# BluetoothMate.net
KiCad netlist of a schematic drawn in EAGLE
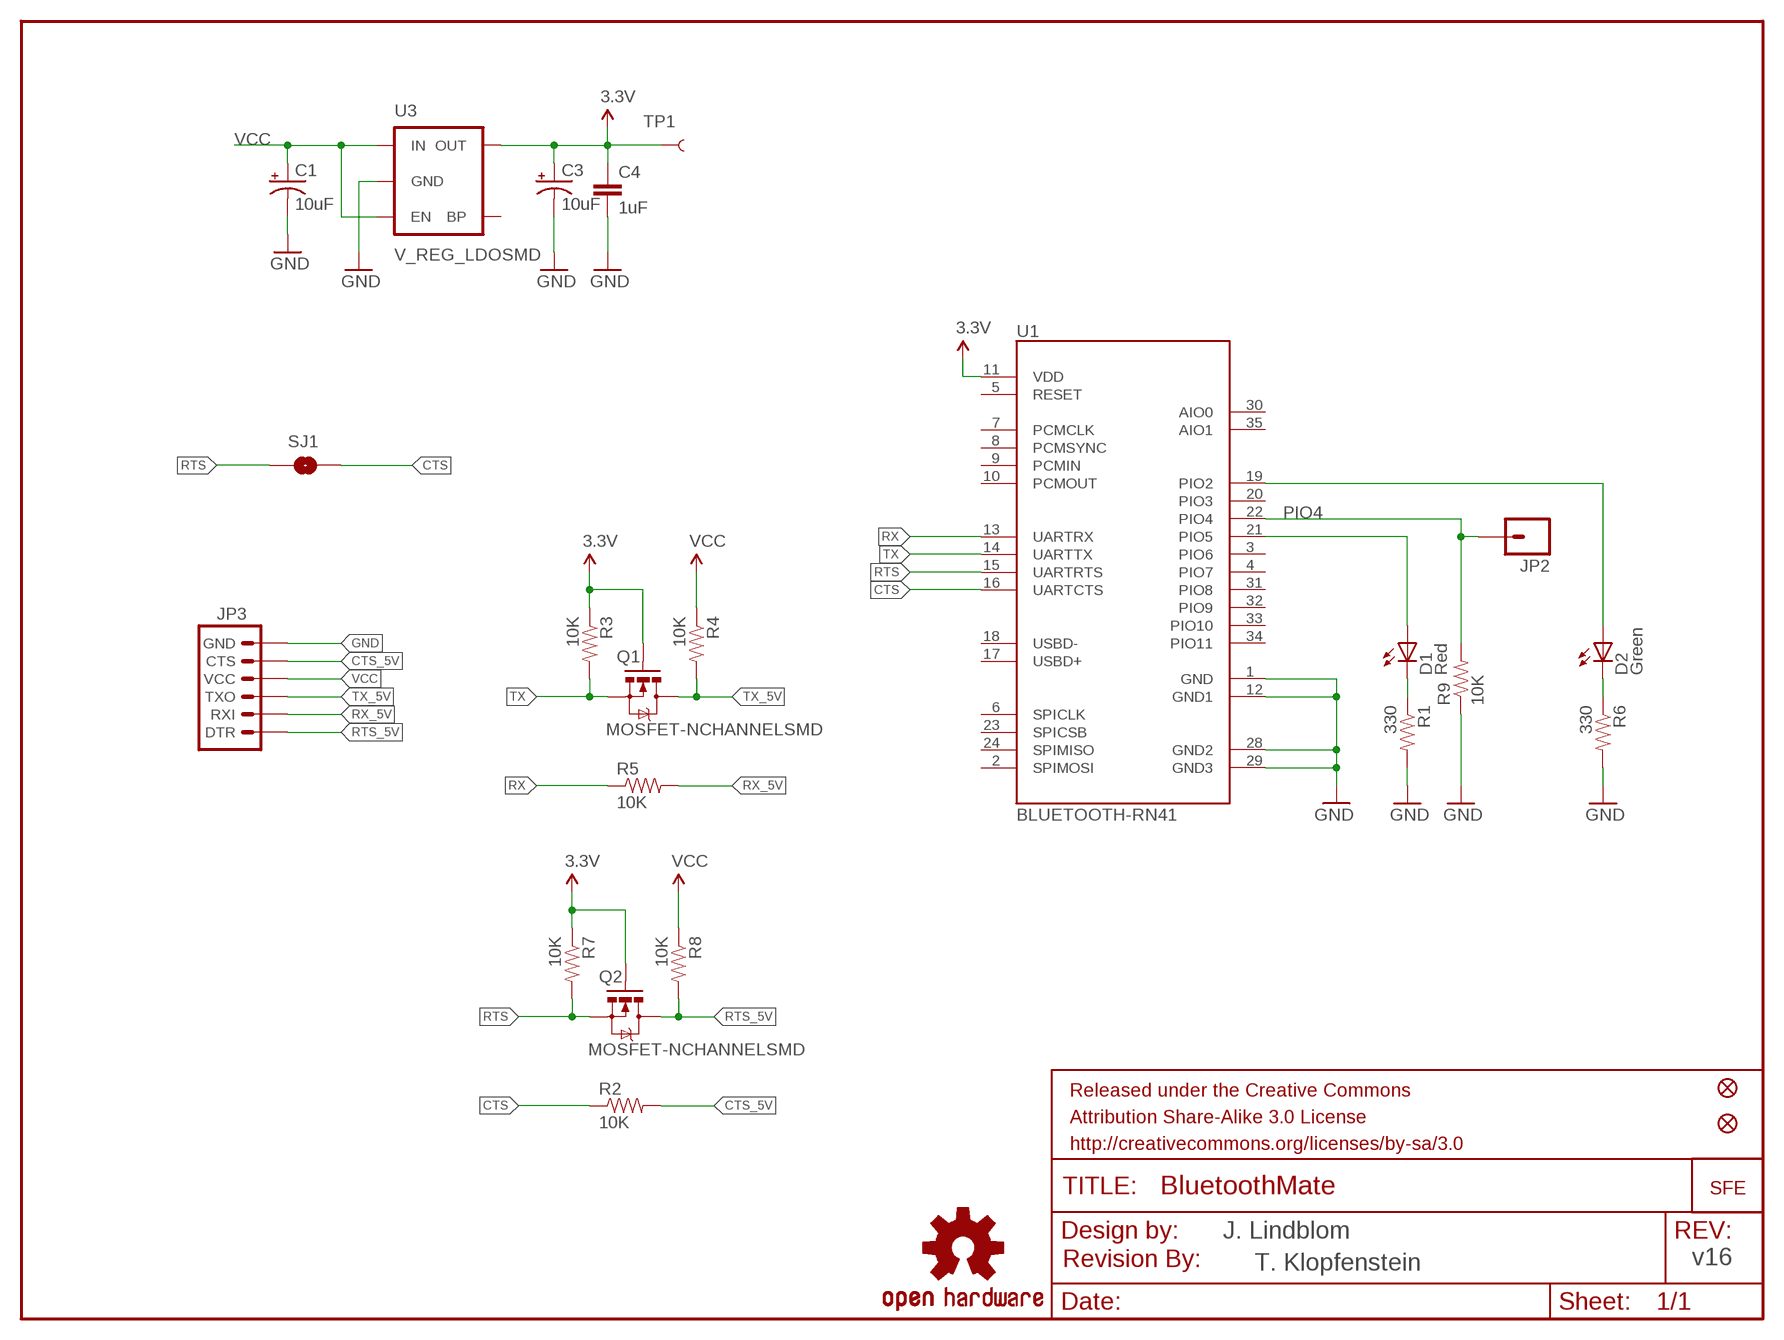
[diagram p0: schematic, sheet 1]

(export (version "E")
  (design (tool "Eeschema 10.0.6"))
  (components
    (comp (ref "C1")
      (value "10uF")
      (footprint "eagle-import:EIA3216")
      (libsource (lib "eagle-import") (part "CAP_POL1206"))
    )
    (comp (ref "C3")
      (value "10uF")
      (footprint "eagle-import:EIA3216")
      (libsource (lib "eagle-import") (part "CAP_POL1206"))
    )
    (comp (ref "C4")
      (value "1uF")
      (footprint "eagle-import:0603-CAP")
      (libsource (lib "eagle-import") (part "CAP0603-CAP"))
    )
    (comp (ref "D1")
      (value "Red")
      (footprint "eagle-import:LED-0603")
      (libsource (lib "eagle-import") (part "LED0603"))
    )
    (comp (ref "D2")
      (value "Green")
      (footprint "eagle-import:LED-0603")
      (libsource (lib "eagle-import") (part "LED0603"))
    )
    (comp (ref "FRAME1")
      (value "FRAME-LETTER")
      (footprint "eagle-import:CREATIVE_COMMONS")
      (libsource (lib "eagle-import") (part "FRAME-LETTER"))
    )
    (comp (ref "JP1")
      (value "FIDUCIAL1X2.5")
      (footprint "eagle-import:FIDUCIAL-1X2.5")
      (libsource (lib "eagle-import") (part "FIDUCIAL1X2.5"))
    )
    (comp (ref "JP2")
      (value "M01SMDNS")
      (footprint "eagle-import:1X01NS")
      (libsource (lib "eagle-import") (part "M01SMDNS"))
    )
    (comp (ref "JP3")
      (value "ARDUINO_SERIAL_PROGRAMPTH")
      (footprint "eagle-import:1X06")
      (libsource (lib "eagle-import") (part "ARDUINO_SERIAL_PROGRAMPTH"))
    )
    (comp (ref "JP4")
      (value "FIDUCIAL1X2.5")
      (footprint "eagle-import:FIDUCIAL-1X2.5")
      (libsource (lib "eagle-import") (part "FIDUCIAL1X2.5"))
    )
    (comp (ref "LOGO1")
      (value "OSHW-LOGOS")
      (footprint "eagle-import:OSHW-LOGO-S")
      (libsource (lib "eagle-import") (part "OSHW-LOGOS"))
    )
    (comp (ref "Q1")
      (value "MOSFET-NCHANNELSMD")
      (footprint "eagle-import:SOT23-3")
      (libsource (lib "eagle-import") (part "MOSFET-NCHANNELSMD"))
    )
    (comp (ref "Q2")
      (value "MOSFET-NCHANNELSMD")
      (footprint "eagle-import:SOT23-3")
      (libsource (lib "eagle-import") (part "MOSFET-NCHANNELSMD"))
    )
    (comp (ref "R1")
      (value "330")
      (footprint "eagle-import:0603-RES")
      (libsource (lib "eagle-import") (part "RESISTOR0603-RES"))
    )
    (comp (ref "R2")
      (value "10K")
      (footprint "eagle-import:0603-RES")
      (libsource (lib "eagle-import") (part "RESISTOR0603-RES"))
    )
    (comp (ref "R3")
      (value "10K")
      (footprint "eagle-import:0603-RES")
      (libsource (lib "eagle-import") (part "RESISTOR0603-RES"))
    )
    (comp (ref "R4")
      (value "10K")
      (footprint "eagle-import:0603-RES")
      (libsource (lib "eagle-import") (part "RESISTOR0603-RES"))
    )
    (comp (ref "R5")
      (value "10K")
      (footprint "eagle-import:0603-RES")
      (libsource (lib "eagle-import") (part "RESISTOR0603-RES"))
    )
    (comp (ref "R6")
      (value "330")
      (footprint "eagle-import:0603-RES")
      (libsource (lib "eagle-import") (part "RESISTOR0603-RES"))
    )
    (comp (ref "R7")
      (value "10K")
      (footprint "eagle-import:0603-RES")
      (libsource (lib "eagle-import") (part "RESISTOR0603-RES"))
    )
    (comp (ref "R8")
      (value "10K")
      (footprint "eagle-import:0603-RES")
      (libsource (lib "eagle-import") (part "RESISTOR0603-RES"))
    )
    (comp (ref "R9")
      (value "10K")
      (footprint "eagle-import:0603-RES")
      (libsource (lib "eagle-import") (part "RESISTOR0603-RES"))
    )
    (comp (ref "SJ1")
      (value "SOLDERJUMPERNO")
      (footprint "eagle-import:SJ_2S-NO")
      (libsource (lib "eagle-import") (part "SOLDERJUMPERNO"))
    )
    (comp (ref "TP1")
      (value "TEST-POINT3X5")
      (footprint "eagle-import:PAD.03X.05")
      (libsource (lib "eagle-import") (part "TEST-POINT3X5"))
    )
    (comp (ref "U$1")
      (value "LOGO-SFENEW")
      (footprint "eagle-import:SFE-NEW-WEBLOGO")
      (libsource (lib "eagle-import") (part "LOGO-SFENEW"))
    )
    (comp (ref "U$2")
      (value "REVISION")
      (footprint "eagle-import:REVISION")
      (libsource (lib "eagle-import") (part "REVISION"))
    )
    (comp (ref "U1")
      (value "BLUETOOTH-RN41")
      (footprint "eagle-import:RN41")
      (libsource (lib "eagle-import") (part "BLUETOOTH-RN41{dblquote}"))
    )
    (comp (ref "U3")
      (value "V_REG_LDOSMD")
      (footprint "eagle-import:SOT23-5")
      (libsource (lib "eagle-import") (part "V_REG_LDOSMD"))
    )
  )
  (nets
    (net (code "1") (name "/PIO4") (class "Default")
      (node (ref "JP2") (pin "1") (pinfunction "1_1") (pintype "passive"))
      (node (ref "R9") (pin "2") (pinfunction "2_2") (pintype "passive"))
      (node (ref "U1") (pin "22") (pinfunction "PIO4_22") (pintype "bidirectional"))
    )
    (net (code "2") (name "3.3V") (class "Default")
      (node (ref "C3") (pin "A") (pinfunction "+_A") (pintype "passive"))
      (node (ref "C4") (pin "1") (pinfunction "1_1") (pintype "passive"))
      (node (ref "Q1") (pin "1") (pinfunction "G_1") (pintype "passive"))
      (node (ref "Q2") (pin "1") (pinfunction "G_1") (pintype "passive"))
      (node (ref "R3") (pin "1") (pinfunction "1_1") (pintype "passive"))
      (node (ref "R7") (pin "1") (pinfunction "1_1") (pintype "passive"))
      (node (ref "TP1") (pin "P$1") (pinfunction "1_P$1") (pintype "bidirectional"))
      (node (ref "U1") (pin "11") (pinfunction "VDD_11") (pintype "bidirectional"))
      (node (ref "U3") (pin "5") (pinfunction "OUT_5") (pintype "passive"))
    )
    (net (code "3") (name "CTS") (class "Default")
      (node (ref "R2") (pin "1") (pinfunction "1_1") (pintype "passive"))
      (node (ref "SJ1") (pin "2") (pinfunction "2_2") (pintype "passive"))
      (node (ref "U1") (pin "16") (pinfunction "UARTCTS_16") (pintype "bidirectional"))
    )
    (net (code "4") (name "CTS_5V") (class "Default")
      (node (ref "JP3") (pin "5") (pinfunction "CTS_5") (pintype "passive"))
      (node (ref "R2") (pin "2") (pinfunction "2_2") (pintype "passive"))
    )
    (net (code "5") (name "GND") (class "Default")
      (node (ref "C1") (pin "C") (pinfunction "-_C") (pintype "passive"))
      (node (ref "C3") (pin "C") (pinfunction "-_C") (pintype "passive"))
      (node (ref "C4") (pin "2") (pinfunction "2_2") (pintype "passive"))
      (node (ref "JP3") (pin "6") (pinfunction "GND_6") (pintype "passive"))
      (node (ref "R1") (pin "2") (pinfunction "2_2") (pintype "passive"))
      (node (ref "R6") (pin "2") (pinfunction "2_2") (pintype "passive"))
      (node (ref "R9") (pin "1") (pinfunction "1_1") (pintype "passive"))
      (node (ref "U1") (pin "1") (pinfunction "GND_1") (pintype "bidirectional"))
      (node (ref "U1") (pin "12") (pinfunction "GND1_12") (pintype "bidirectional"))
      (node (ref "U1") (pin "28") (pinfunction "GND2_28") (pintype "bidirectional"))
      (node (ref "U1") (pin "29") (pinfunction "GND3_29") (pintype "bidirectional"))
      (node (ref "U3") (pin "2") (pinfunction "GND_2") (pintype "input"))
    )
    (net (code "6") (name "Net-(D1-PadC)") (class "Default")
      (node (ref "D1") (pin "C") (pinfunction "C_C") (pintype "passive"))
      (node (ref "R1") (pin "1") (pinfunction "1_1") (pintype "passive"))
    )
    (net (code "7") (name "Net-(D2-PadC)") (class "Default")
      (node (ref "D2") (pin "C") (pinfunction "C_C") (pintype "passive"))
      (node (ref "R6") (pin "1") (pinfunction "1_1") (pintype "passive"))
    )
    (net (code "8") (name "Net-(U1-PIO2)") (class "Default")
      (node (ref "D2") (pin "A") (pinfunction "A_A") (pintype "passive"))
      (node (ref "U1") (pin "19") (pinfunction "PIO2_19") (pintype "bidirectional"))
    )
    (net (code "9") (name "Net-(U1-PIO5)") (class "Default")
      (node (ref "D1") (pin "A") (pinfunction "A_A") (pintype "passive"))
      (node (ref "U1") (pin "21") (pinfunction "PIO5_21") (pintype "bidirectional"))
    )
    (net (code "10") (name "RTS") (class "Default")
      (node (ref "Q2") (pin "2") (pinfunction "S_2") (pintype "passive"))
      (node (ref "R7") (pin "2") (pinfunction "2_2") (pintype "passive"))
      (node (ref "SJ1") (pin "1") (pinfunction "1_1") (pintype "passive"))
      (node (ref "U1") (pin "15") (pinfunction "UARTRTS_15") (pintype "bidirectional"))
    )
    (net (code "11") (name "RTS_5V") (class "Default")
      (node (ref "JP3") (pin "1") (pinfunction "DTR_1") (pintype "passive"))
      (node (ref "Q2") (pin "3") (pinfunction "D_3") (pintype "passive"))
      (node (ref "R8") (pin "2") (pinfunction "2_2") (pintype "passive"))
    )
    (net (code "12") (name "RX") (class "Default")
      (node (ref "R5") (pin "1") (pinfunction "1_1") (pintype "passive"))
      (node (ref "U1") (pin "13") (pinfunction "UARTRX_13") (pintype "bidirectional"))
    )
    (net (code "13") (name "RX_5V") (class "Default")
      (node (ref "JP3") (pin "2") (pinfunction "RXI_2") (pintype "passive"))
      (node (ref "R5") (pin "2") (pinfunction "2_2") (pintype "passive"))
    )
    (net (code "14") (name "TX") (class "Default")
      (node (ref "Q1") (pin "2") (pinfunction "S_2") (pintype "passive"))
      (node (ref "R3") (pin "2") (pinfunction "2_2") (pintype "passive"))
      (node (ref "U1") (pin "14") (pinfunction "UARTTX_14") (pintype "bidirectional"))
    )
    (net (code "15") (name "TX_5V") (class "Default")
      (node (ref "JP3") (pin "3") (pinfunction "TXO_3") (pintype "passive"))
      (node (ref "Q1") (pin "3") (pinfunction "D_3") (pintype "passive"))
      (node (ref "R4") (pin "2") (pinfunction "2_2") (pintype "passive"))
    )
    (net (code "16") (name "VCC") (class "Default")
      (node (ref "C1") (pin "A") (pinfunction "+_A") (pintype "passive"))
      (node (ref "JP3") (pin "4") (pinfunction "VCC_4") (pintype "passive"))
      (node (ref "R4") (pin "1") (pinfunction "1_1") (pintype "passive"))
      (node (ref "R8") (pin "1") (pinfunction "1_1") (pintype "passive"))
      (node (ref "U3") (pin "1") (pinfunction "IN_1") (pintype "input"))
      (node (ref "U3") (pin "3") (pinfunction "EN_3") (pintype "input"))
    )
    (net (code "17") (name "unconnected-(U1-AIO0-Pad30)") (class "Default")
      (node (ref "U1") (pin "30") (pinfunction "AIO0_30") (pintype "bidirectional"))
    )
    (net (code "18") (name "unconnected-(U1-AIO1-Pad35)") (class "Default")
      (node (ref "U1") (pin "35") (pinfunction "AIO1_35") (pintype "bidirectional"))
    )
    (net (code "19") (name "unconnected-(U1-PCMCLK-Pad7)") (class "Default")
      (node (ref "U1") (pin "7") (pinfunction "PCMCLK_7") (pintype "bidirectional"))
    )
    (net (code "20") (name "unconnected-(U1-PCMIN-Pad9)") (class "Default")
      (node (ref "U1") (pin "9") (pinfunction "PCMIN_9") (pintype "bidirectional"))
    )
    (net (code "21") (name "unconnected-(U1-PCMOUT-Pad10)") (class "Default")
      (node (ref "U1") (pin "10") (pinfunction "PCMOUT_10") (pintype "bidirectional"))
    )
    (net (code "22") (name "unconnected-(U1-PCMSYNC-Pad8)") (class "Default")
      (node (ref "U1") (pin "8") (pinfunction "PCMSYNC_8") (pintype "bidirectional"))
    )
    (net (code "23") (name "unconnected-(U1-PIO3-Pad20)") (class "Default")
      (node (ref "U1") (pin "20") (pinfunction "PIO3_20") (pintype "bidirectional"))
    )
    (net (code "24") (name "unconnected-(U1-PIO6-Pad3)") (class "Default")
      (node (ref "U1") (pin "3") (pinfunction "PIO6_3") (pintype "bidirectional"))
    )
    (net (code "25") (name "unconnected-(U1-PIO7-Pad4)") (class "Default")
      (node (ref "U1") (pin "4") (pinfunction "PIO7_4") (pintype "bidirectional"))
    )
    (net (code "26") (name "unconnected-(U1-PIO8-Pad31)") (class "Default")
      (node (ref "U1") (pin "31") (pinfunction "PIO8_31") (pintype "bidirectional"))
    )
    (net (code "27") (name "unconnected-(U1-PIO9-Pad32)") (class "Default")
      (node (ref "U1") (pin "32") (pinfunction "PIO9_32") (pintype "bidirectional"))
    )
    (net (code "28") (name "unconnected-(U1-PIO10-Pad33)") (class "Default")
      (node (ref "U1") (pin "33") (pinfunction "PIO10_33") (pintype "bidirectional"))
    )
    (net (code "29") (name "unconnected-(U1-PIO11-Pad34)") (class "Default")
      (node (ref "U1") (pin "34") (pinfunction "PIO11_34") (pintype "bidirectional"))
    )
    (net (code "30") (name "unconnected-(U1-RESET-Pad5)") (class "Default")
      (node (ref "U1") (pin "5") (pinfunction "RESET_5") (pintype "bidirectional"))
    )
    (net (code "31") (name "unconnected-(U1-SPICLK-Pad6)") (class "Default")
      (node (ref "U1") (pin "6") (pinfunction "SPICLK_6") (pintype "bidirectional"))
    )
    (net (code "32") (name "unconnected-(U1-SPICSB-Pad23)") (class "Default")
      (node (ref "U1") (pin "23") (pinfunction "SPICSB_23") (pintype "bidirectional"))
    )
    (net (code "33") (name "unconnected-(U1-SPIMISO-Pad24)") (class "Default")
      (node (ref "U1") (pin "24") (pinfunction "SPIMISO_24") (pintype "bidirectional"))
    )
    (net (code "34") (name "unconnected-(U1-SPIMOSI-Pad2)") (class "Default")
      (node (ref "U1") (pin "2") (pinfunction "SPIMOSI_2") (pintype "bidirectional"))
    )
    (net (code "35") (name "unconnected-(U1-USBD+-Pad17)") (class "Default")
      (node (ref "U1") (pin "17") (pinfunction "USBD+_17") (pintype "bidirectional"))
    )
    (net (code "36") (name "unconnected-(U1-USBD--Pad18)") (class "Default")
      (node (ref "U1") (pin "18") (pinfunction "USBD-_18") (pintype "bidirectional"))
    )
    (net (code "37") (name "unconnected-(U3-BP-Pad4)") (class "Default")
      (node (ref "U3") (pin "4") (pinfunction "BP_4") (pintype "input"))
    )
  )
)
